# QCopterMV_FSMC_Sch.net
KiCad netlist of a schematic drawn in Altium Designer
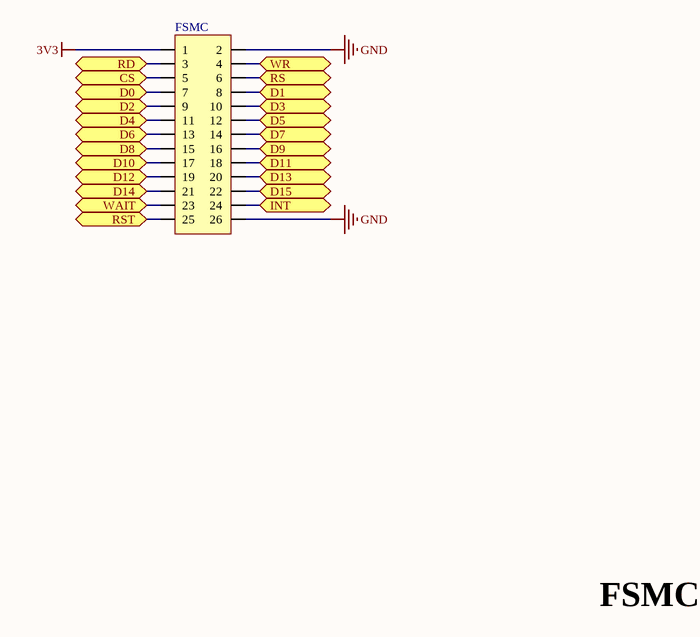
[diagram p0: QCopterMV_FSMC_Sch.SchDoc]

(export (version "E")
  (design (tool "Eeschema 10.0.6"))
  (components
    (comp (ref "FSMC")
      (value "HDR2X13_180FTB_2.54")
      (footprint "PCB_Connector:HDR2X13_180FTB_2.54")
      (description "Header")
      (libsource (lib "SCH_Connector") (part "HDR2X13_180FTB_2.54"))
    )
  )
  (nets
    (net (code "1") (name "/CS") (class "Default")
      (node (ref "FSMC") (pin "5") (pinfunction "5_5") (pintype "passive"))
    )
    (net (code "2") (name "/D0") (class "Default")
      (node (ref "FSMC") (pin "7") (pinfunction "7_7") (pintype "passive"))
    )
    (net (code "3") (name "/D1") (class "Default")
      (node (ref "FSMC") (pin "8") (pinfunction "8_8") (pintype "passive"))
    )
    (net (code "4") (name "/D2") (class "Default")
      (node (ref "FSMC") (pin "9") (pinfunction "9_9") (pintype "passive"))
    )
    (net (code "5") (name "/D3") (class "Default")
      (node (ref "FSMC") (pin "10") (pinfunction "10_10") (pintype "passive"))
    )
    (net (code "6") (name "/D4") (class "Default")
      (node (ref "FSMC") (pin "11") (pinfunction "11_11") (pintype "passive"))
    )
    (net (code "7") (name "/D5") (class "Default")
      (node (ref "FSMC") (pin "12") (pinfunction "12_12") (pintype "passive"))
    )
    (net (code "8") (name "/D6") (class "Default")
      (node (ref "FSMC") (pin "13") (pinfunction "13_13") (pintype "passive"))
    )
    (net (code "9") (name "/D7") (class "Default")
      (node (ref "FSMC") (pin "14") (pinfunction "14_14") (pintype "passive"))
    )
    (net (code "10") (name "/D8") (class "Default")
      (node (ref "FSMC") (pin "15") (pinfunction "15_15") (pintype "passive"))
    )
    (net (code "11") (name "/D9") (class "Default")
      (node (ref "FSMC") (pin "16") (pinfunction "16_16") (pintype "passive"))
    )
    (net (code "12") (name "/D10") (class "Default")
      (node (ref "FSMC") (pin "17") (pinfunction "17_17") (pintype "passive"))
    )
    (net (code "13") (name "/D11") (class "Default")
      (node (ref "FSMC") (pin "18") (pinfunction "18_18") (pintype "passive"))
    )
    (net (code "14") (name "/D12") (class "Default")
      (node (ref "FSMC") (pin "19") (pinfunction "19_19") (pintype "passive"))
    )
    (net (code "15") (name "/D13") (class "Default")
      (node (ref "FSMC") (pin "20") (pinfunction "20_20") (pintype "passive"))
    )
    (net (code "16") (name "/D14") (class "Default")
      (node (ref "FSMC") (pin "21") (pinfunction "21_21") (pintype "passive"))
    )
    (net (code "17") (name "/D15") (class "Default")
      (node (ref "FSMC") (pin "22") (pinfunction "22_22") (pintype "passive"))
    )
    (net (code "18") (name "/INT") (class "Default")
      (node (ref "FSMC") (pin "24") (pinfunction "24_24") (pintype "passive"))
    )
    (net (code "19") (name "/RD") (class "Default")
      (node (ref "FSMC") (pin "3") (pinfunction "3_3") (pintype "passive"))
    )
    (net (code "20") (name "/RS") (class "Default")
      (node (ref "FSMC") (pin "6") (pinfunction "6_6") (pintype "passive"))
    )
    (net (code "21") (name "/RST") (class "Default")
      (node (ref "FSMC") (pin "25") (pinfunction "25_25") (pintype "passive"))
    )
    (net (code "22") (name "/WAIT") (class "Default")
      (node (ref "FSMC") (pin "23") (pinfunction "23_23") (pintype "passive"))
    )
    (net (code "23") (name "/WR") (class "Default")
      (node (ref "FSMC") (pin "4") (pinfunction "4_4") (pintype "passive"))
    )
    (net (code "24") (name "3V3") (class "Default")
      (node (ref "FSMC") (pin "1") (pinfunction "1_1") (pintype "passive"))
    )
    (net (code "25") (name "GND") (class "Default")
      (node (ref "FSMC") (pin "2") (pinfunction "2_2") (pintype "passive"))
      (node (ref "FSMC") (pin "26") (pinfunction "26_26") (pintype "passive"))
    )
  )
)
